# gas_sub_module.net
KiCad netlist of a schematic drawn in EAGLE
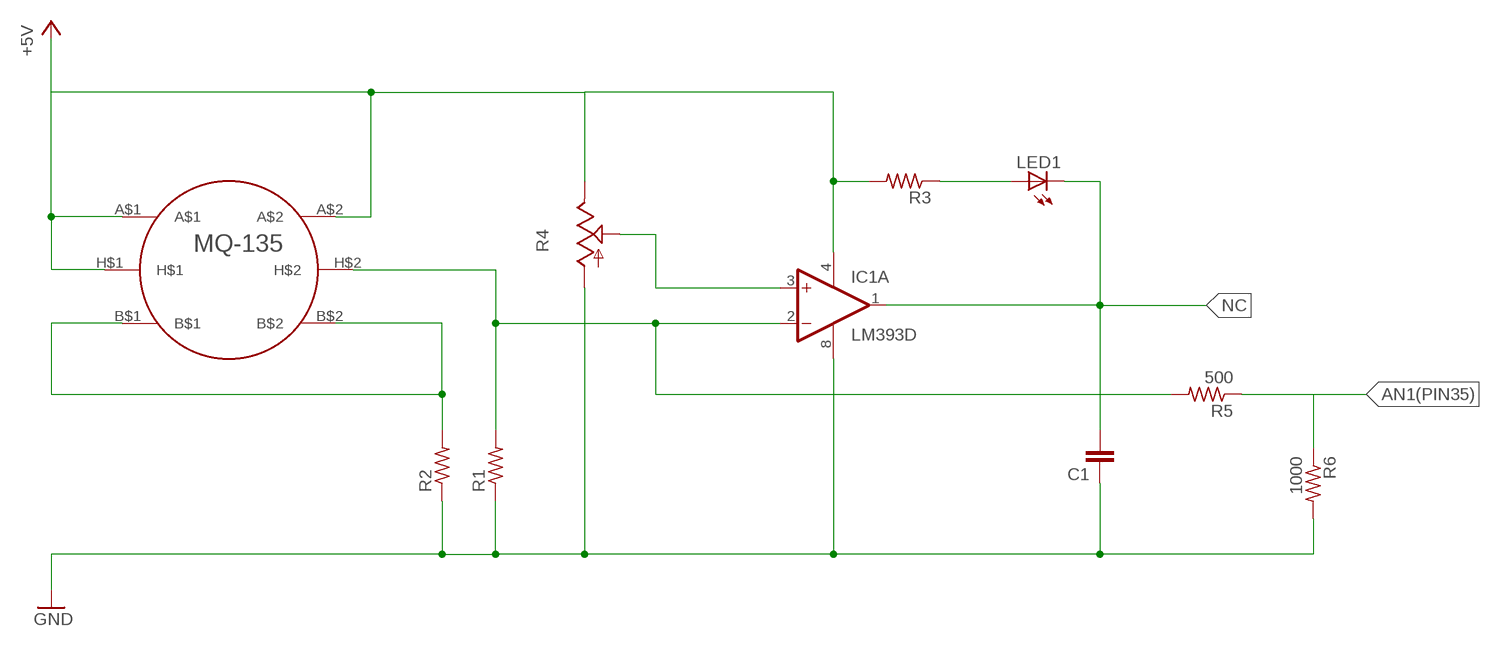
[diagram p0: schematic, sheet 1]

(export (version "E")
  (design (tool "Eeschema 10.0.6"))
  (components
    (comp (ref "C1")
      (value "C-EU025-025X050")
      (footprint "eagle-import:C025-025X050")
      (libsource (lib "eagle-import") (part "C-EU025-025X050"))
    )
    (comp (ref "IC1")
      (value "LM393D")
      (footprint "eagle-import:SO08")
      (libsource (lib "eagle-import") (part "LM393D"))
    )
    (comp (ref "LED1")
      (value "LAP4-BOTTOM")
      (footprint "eagle-import:P47F-BOTTOM")
      (libsource (lib "eagle-import") (part "P4-BOTTOMLA"))
    )
    (comp (ref "R1")
      (value "R-US_0204/2V")
      (footprint "eagle-import:0204V")
      (libsource (lib "eagle-import") (part "R-US_0204/2V"))
    )
    (comp (ref "R2")
      (value "R-US_0204/2V")
      (footprint "eagle-import:0204V")
      (libsource (lib "eagle-import") (part "R-US_0204/2V"))
    )
    (comp (ref "R3")
      (value "R-US_0204/2V")
      (footprint "eagle-import:0204V")
      (libsource (lib "eagle-import") (part "R-US_0204/2V"))
    )
    (comp (ref "R4")
      (value "TRIM_US-3223G")
      (footprint "eagle-import:3223G")
      (libsource (lib "eagle-import") (part "TRIM_US-3223G"))
    )
    (comp (ref "R5")
      (value "500")
      (footprint "eagle-import:0204V")
      (libsource (lib "eagle-import") (part "R-US_0204/2V"))
    )
    (comp (ref "R6")
      (value "1000")
      (footprint "eagle-import:0204V")
      (libsource (lib "eagle-import") (part "R-US_0204/2V"))
    )
    (comp (ref "U$1")
      (value "MQ_135_A")
      (footprint "eagle-import:MQ-135")
      (libsource (lib "eagle-import") (part "MQ_135_A"))
    )
  )
  (nets
    (net (code "1") (name "+5V") (class "Default")
      (node (ref "IC1") (pin "4") (pinfunction "V-_4") (pintype "power_in"))
      (node (ref "R3") (pin "2") (pinfunction "2_2") (pintype "passive"))
      (node (ref "R4") (pin "3") (pinfunction "E_3") (pintype "passive"))
      (node (ref "U$1") (pin "A$1") (pinfunction "A$1_A$1") (pintype "bidirectional"))
      (node (ref "U$1") (pin "A$2") (pinfunction "A$2_A$2") (pintype "bidirectional"))
      (node (ref "U$1") (pin "H$1") (pinfunction "H$1_H$1") (pintype "bidirectional"))
    )
    (net (code "2") (name "AN1(PIN35)") (class "Default")
      (node (ref "R5") (pin "1") (pinfunction "1_1") (pintype "passive"))
      (node (ref "R6") (pin "1") (pinfunction "1_1") (pintype "passive"))
    )
    (net (code "3") (name "GND") (class "Default")
      (node (ref "C1") (pin "1") (pinfunction "1_1") (pintype "passive"))
      (node (ref "IC1") (pin "8") (pinfunction "V+_8") (pintype "power_in"))
      (node (ref "R1") (pin "1") (pinfunction "1_1") (pintype "passive"))
      (node (ref "R2") (pin "1") (pinfunction "1_1") (pintype "passive"))
      (node (ref "R4") (pin "1") (pinfunction "A_1") (pintype "passive"))
      (node (ref "R6") (pin "2") (pinfunction "2_2") (pintype "passive"))
    )
    (net (code "4") (name "NC") (class "Default")
      (node (ref "C1") (pin "2") (pinfunction "2_2") (pintype "passive"))
      (node (ref "IC1") (pin "1") (pinfunction "OUT_1") (pintype "output"))
      (node (ref "LED1") (pin "C") (pinfunction "C_C") (pintype "passive"))
    )
    (net (code "5") (name "Net-(IC1A-+IN)") (class "Default")
      (node (ref "IC1") (pin "3") (pinfunction "+IN_3") (pintype "input"))
      (node (ref "R4") (pin "2") (pinfunction "S_2") (pintype "passive"))
    )
    (net (code "6") (name "Net-(IC1A--IN)") (class "Default")
      (node (ref "IC1") (pin "2") (pinfunction "-IN_2") (pintype "input"))
      (node (ref "R1") (pin "2") (pinfunction "2_2") (pintype "passive"))
      (node (ref "R5") (pin "2") (pinfunction "2_2") (pintype "passive"))
      (node (ref "U$1") (pin "H$2") (pinfunction "H$2_H$2") (pintype "bidirectional"))
    )
    (net (code "7") (name "Net-(LED1-PadA)") (class "Default")
      (node (ref "LED1") (pin "A") (pinfunction "A_A") (pintype "passive"))
      (node (ref "R3") (pin "1") (pinfunction "1_1") (pintype "passive"))
    )
    (net (code "8") (name "Net-(R2-Pad2)") (class "Default")
      (node (ref "R2") (pin "2") (pinfunction "2_2") (pintype "passive"))
      (node (ref "U$1") (pin "B$1") (pinfunction "B$1_B$1") (pintype "bidirectional"))
      (node (ref "U$1") (pin "B$2") (pinfunction "B$2_B$2") (pintype "bidirectional"))
    )
  )
)
